# pyIMU_v1.net
KiCad netlist of a schematic drawn in EAGLE
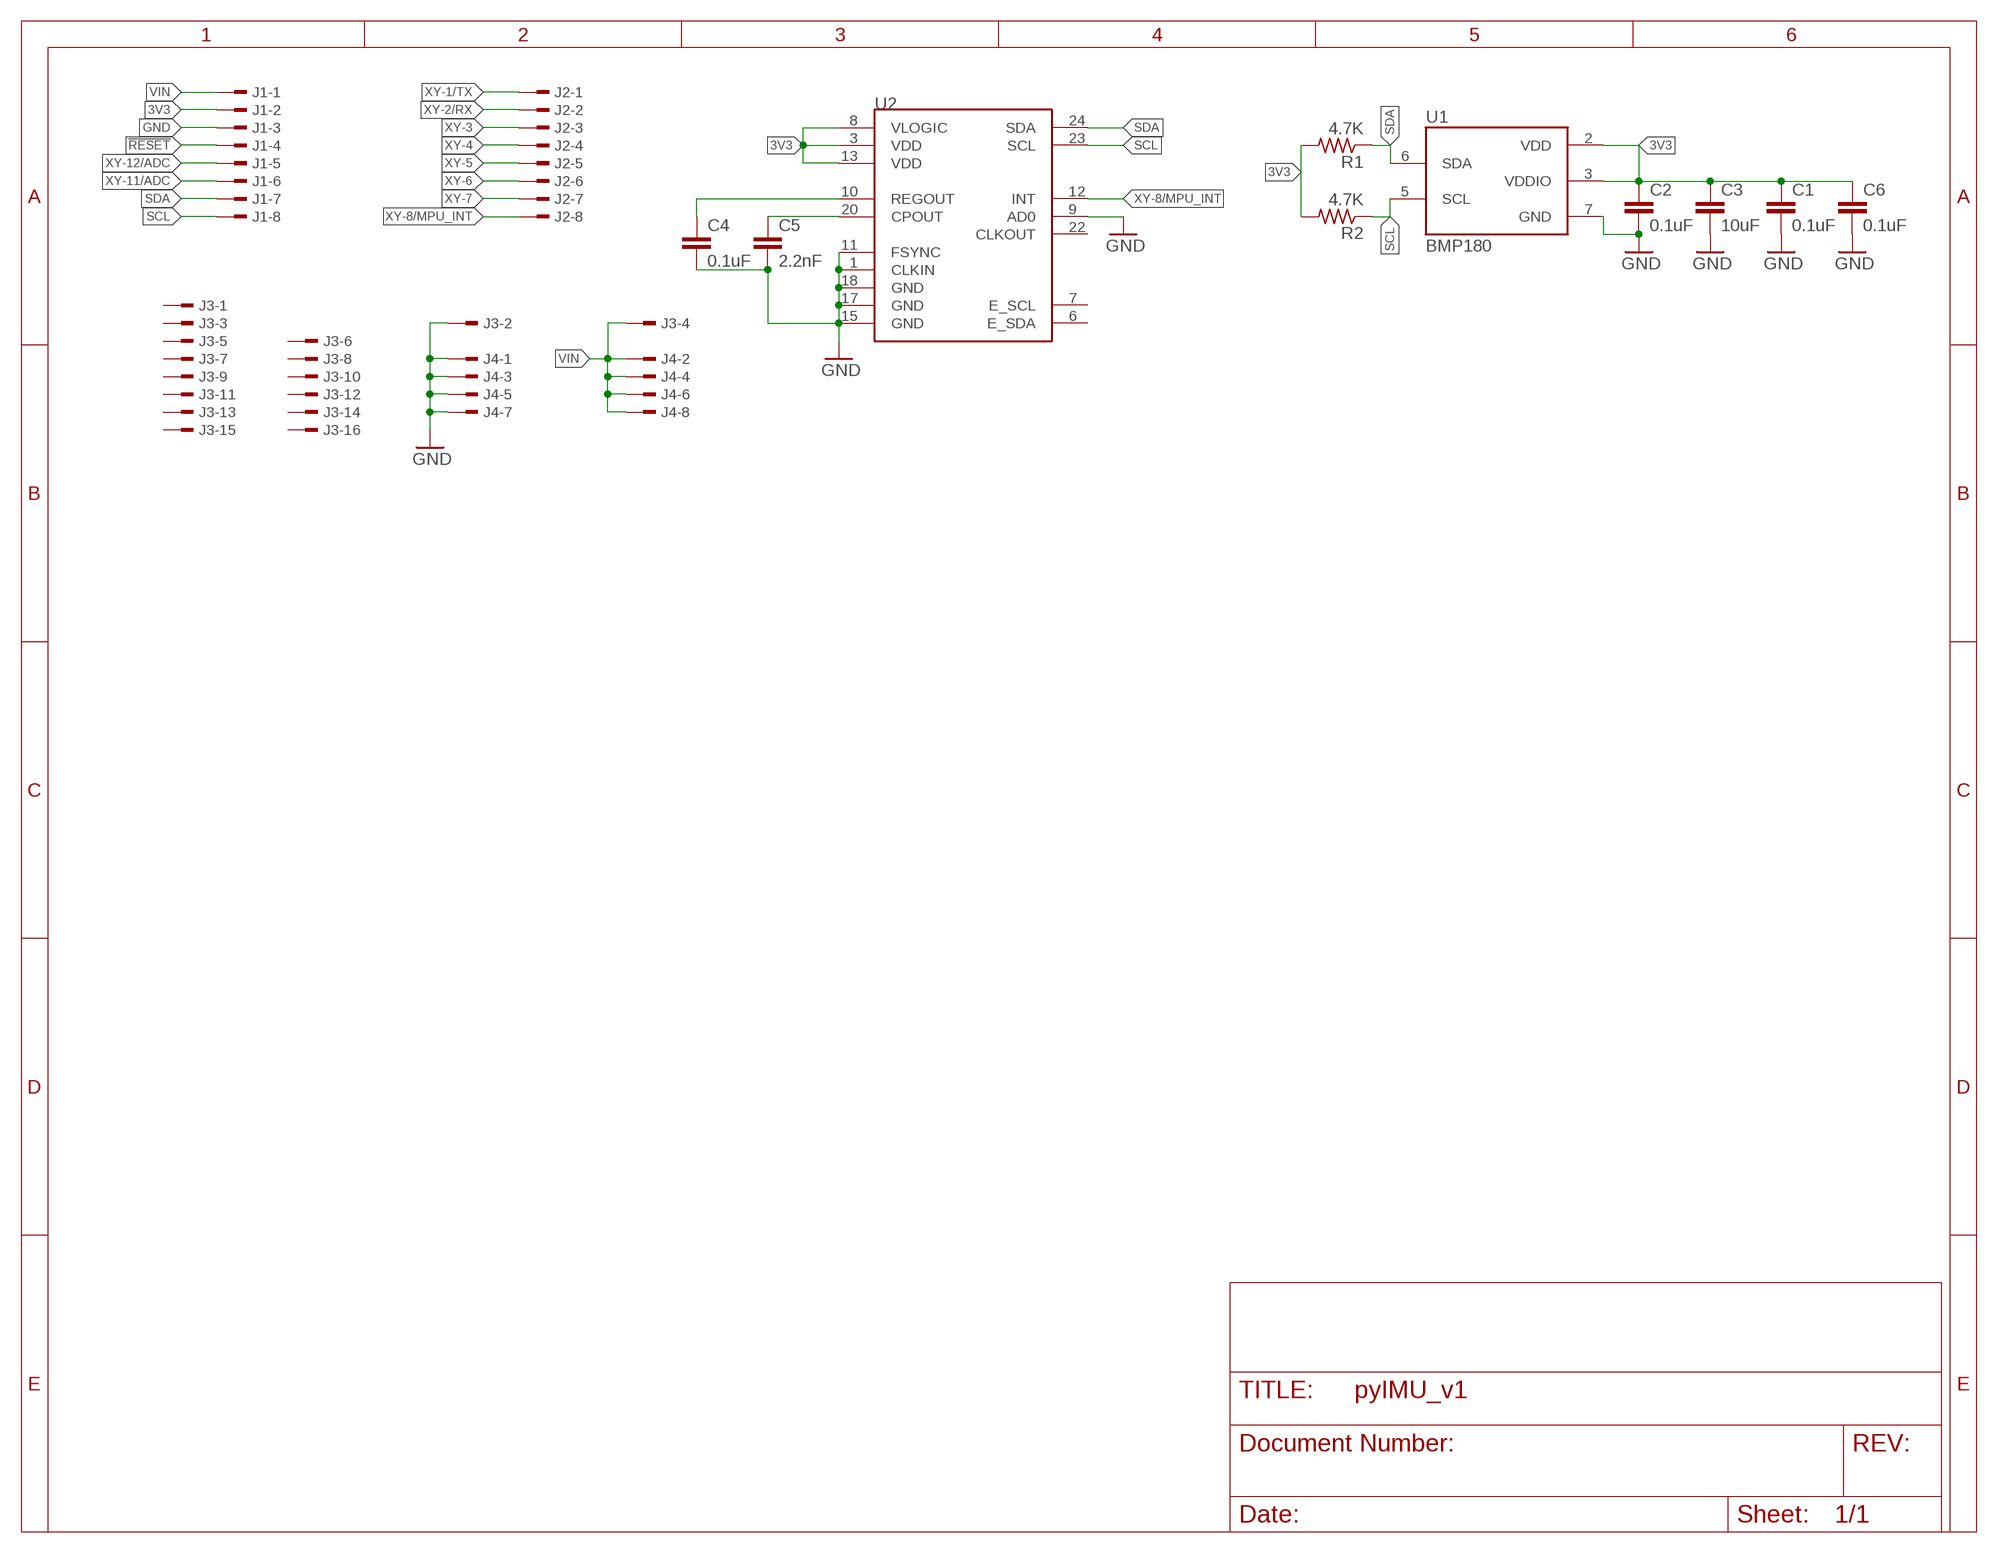
[diagram p0: schematic, sheet 1]

(export (version "E")
  (design (tool "Eeschema 10.0.6"))
  (components
    (comp (ref "C1")
      (value "0.1uF")
      (footprint "eagle-import:C0603K")
      (libsource (lib "eagle-import") (part "C-EUC0603K"))
    )
    (comp (ref "C2")
      (value "0.1uF")
      (footprint "eagle-import:C0603K")
      (libsource (lib "eagle-import") (part "C-EUC0603K"))
    )
    (comp (ref "C3")
      (value "10uF")
      (footprint "eagle-import:C0603K")
      (libsource (lib "eagle-import") (part "C-EUC0603K"))
    )
    (comp (ref "C4")
      (value "0.1uF")
      (footprint "eagle-import:C0603K")
      (libsource (lib "eagle-import") (part "C-EUC0603K"))
    )
    (comp (ref "C5")
      (value "2.2nF")
      (footprint "eagle-import:C0603K")
      (libsource (lib "eagle-import") (part "C-EUC0603K"))
    )
    (comp (ref "C6")
      (value "0.1uF")
      (footprint "eagle-import:C0603K")
      (libsource (lib "eagle-import") (part "C-EUC0603K"))
    )
    (comp (ref "J1")
      (value "TSW-108-02-S-S-MOD")
      (footprint "eagle-import:TSW-108-02-S-S-MOD")
      (libsource (lib "eagle-import") (part "TSW-108-02-S-S-MOD"))
    )
    (comp (ref "J2")
      (value "TSW-108-02-S-S-MOD")
      (footprint "eagle-import:TSW-108-02-S-S-MOD")
      (libsource (lib "eagle-import") (part "TSW-108-02-S-S-MOD"))
    )
    (comp (ref "J3")
      (value "TSW-108-02-S-D-MOD")
      (footprint "eagle-import:TSW-108-02-S-D-MOD")
      (libsource (lib "eagle-import") (part "TSW-108-02-S-D-MOD"))
    )
    (comp (ref "J4")
      (value "TSW-104-02-S-D-MOD")
      (footprint "eagle-import:TSW-104-02-S-D-MOD")
      (libsource (lib "eagle-import") (part "TSW-104-02-S-D-MOD"))
    )
    (comp (ref "R1")
      (value "4.7K")
      (footprint "eagle-import:R0603")
      (libsource (lib "eagle-import") (part "R-US_R0603"))
    )
    (comp (ref "R2")
      (value "4.7K")
      (footprint "eagle-import:R0603")
      (libsource (lib "eagle-import") (part "R-US_R0603"))
    )
    (comp (ref "U1")
      (value "BMP180")
      (footprint "eagle-import:BMP180")
      (libsource (lib "eagle-import") (part "BMP180"))
    )
    (comp (ref "U2")
      (value "MPU-9150QFN-24-NP")
      (footprint "eagle-import:QFN-24-NP")
      (libsource (lib "eagle-import") (part "MPU-9150QFN-24-NP"))
    )
  )
  (nets
    (net (code "1") (name "/~{RESET}") (class "Default")
      (node (ref "J1") (pin "4") (pinfunction "1_4") (pintype "passive"))
    )
    (net (code "2") (name "3V3") (class "Default")
      (node (ref "C1") (pin "1") (pinfunction "1_1") (pintype "passive"))
      (node (ref "C2") (pin "1") (pinfunction "1_1") (pintype "passive"))
      (node (ref "C3") (pin "1") (pinfunction "1_1") (pintype "passive"))
      (node (ref "C6") (pin "1") (pinfunction "1_1") (pintype "passive"))
      (node (ref "J1") (pin "2") (pinfunction "1_2") (pintype "passive"))
      (node (ref "R1") (pin "2") (pinfunction "2_2") (pintype "passive"))
      (node (ref "R2") (pin "2") (pinfunction "2_2") (pintype "passive"))
      (node (ref "U1") (pin "2") (pinfunction "VDD_2") (pintype "power_in"))
      (node (ref "U1") (pin "3") (pinfunction "VDDIO_3") (pintype "power_in"))
      (node (ref "U2") (pin "13") (pinfunction "VDD_13") (pintype "bidirectional"))
      (node (ref "U2") (pin "3") (pinfunction "VDD_3") (pintype "bidirectional"))
      (node (ref "U2") (pin "8") (pinfunction "VLOGIC_8") (pintype "bidirectional"))
    )
    (net (code "3") (name "GND") (class "Default")
      (node (ref "C1") (pin "2") (pinfunction "2_2") (pintype "passive"))
      (node (ref "C2") (pin "2") (pinfunction "2_2") (pintype "passive"))
      (node (ref "C3") (pin "2") (pinfunction "2_2") (pintype "passive"))
      (node (ref "C4") (pin "2") (pinfunction "2_2") (pintype "passive"))
      (node (ref "C5") (pin "2") (pinfunction "2_2") (pintype "passive"))
      (node (ref "C6") (pin "2") (pinfunction "2_2") (pintype "passive"))
      (node (ref "J1") (pin "3") (pinfunction "1_3") (pintype "passive"))
      (node (ref "J3") (pin "2") (pinfunction "1_2") (pintype "passive"))
      (node (ref "J4") (pin "1") (pinfunction "1_1") (pintype "passive"))
      (node (ref "J4") (pin "3") (pinfunction "1_3") (pintype "passive"))
      (node (ref "J4") (pin "5") (pinfunction "1_5") (pintype "passive"))
      (node (ref "J4") (pin "7") (pinfunction "1_7") (pintype "passive"))
      (node (ref "U1") (pin "7") (pinfunction "GND_7") (pintype "power_in"))
      (node (ref "U2") (pin "1") (pinfunction "CLKIN_1") (pintype "bidirectional"))
      (node (ref "U2") (pin "11") (pinfunction "FSYNC_11") (pintype "bidirectional"))
      (node (ref "U2") (pin "15") (pinfunction "GND_15") (pintype "bidirectional"))
      (node (ref "U2") (pin "17") (pinfunction "GND_17") (pintype "bidirectional"))
      (node (ref "U2") (pin "18") (pinfunction "GND_18") (pintype "bidirectional"))
      (node (ref "U2") (pin "9") (pinfunction "AD0_9") (pintype "bidirectional"))
    )
    (net (code "4") (name "Net-(U2-CPOUT)") (class "Default")
      (node (ref "C5") (pin "1") (pinfunction "1_1") (pintype "passive"))
      (node (ref "U2") (pin "20") (pinfunction "CPOUT_20") (pintype "bidirectional"))
    )
    (net (code "5") (name "Net-(U2-REGOUT)") (class "Default")
      (node (ref "C4") (pin "1") (pinfunction "1_1") (pintype "passive"))
      (node (ref "U2") (pin "10") (pinfunction "REGOUT_10") (pintype "bidirectional"))
    )
    (net (code "6") (name "SCL") (class "Default")
      (node (ref "J1") (pin "8") (pinfunction "1_8") (pintype "passive"))
      (node (ref "R2") (pin "1") (pinfunction "1_1") (pintype "passive"))
      (node (ref "U1") (pin "5") (pinfunction "SCL_5") (pintype "input"))
      (node (ref "U2") (pin "23") (pinfunction "SCL_23") (pintype "bidirectional"))
    )
    (net (code "7") (name "SDA") (class "Default")
      (node (ref "J1") (pin "7") (pinfunction "1_7") (pintype "passive"))
      (node (ref "R1") (pin "1") (pinfunction "1_1") (pintype "passive"))
      (node (ref "U1") (pin "6") (pinfunction "SDA_6") (pintype "bidirectional"))
      (node (ref "U2") (pin "24") (pinfunction "SDA_24") (pintype "bidirectional"))
    )
    (net (code "8") (name "VIN") (class "Default")
      (node (ref "J1") (pin "1") (pinfunction "1_1") (pintype "passive"))
      (node (ref "J3") (pin "4") (pinfunction "1_4") (pintype "passive"))
      (node (ref "J4") (pin "2") (pinfunction "1_2") (pintype "passive"))
      (node (ref "J4") (pin "4") (pinfunction "1_4") (pintype "passive"))
      (node (ref "J4") (pin "6") (pinfunction "1_6") (pintype "passive"))
      (node (ref "J4") (pin "8") (pinfunction "1_8") (pintype "passive"))
    )
    (net (code "9") (name "XY-1{slash}TX") (class "Default")
      (node (ref "J2") (pin "1") (pinfunction "1_1") (pintype "passive"))
    )
    (net (code "10") (name "XY-2{slash}RX") (class "Default")
      (node (ref "J2") (pin "2") (pinfunction "1_2") (pintype "passive"))
    )
    (net (code "11") (name "XY-3") (class "Default")
      (node (ref "J2") (pin "3") (pinfunction "1_3") (pintype "passive"))
    )
    (net (code "12") (name "XY-4") (class "Default")
      (node (ref "J2") (pin "4") (pinfunction "1_4") (pintype "passive"))
    )
    (net (code "13") (name "XY-5") (class "Default")
      (node (ref "J2") (pin "5") (pinfunction "1_5") (pintype "passive"))
    )
    (net (code "14") (name "XY-6") (class "Default")
      (node (ref "J2") (pin "6") (pinfunction "1_6") (pintype "passive"))
    )
    (net (code "15") (name "XY-7") (class "Default")
      (node (ref "J2") (pin "7") (pinfunction "1_7") (pintype "passive"))
    )
    (net (code "16") (name "XY-8{slash}MPU_INT") (class "Default")
      (node (ref "J2") (pin "8") (pinfunction "1_8") (pintype "passive"))
      (node (ref "U2") (pin "12") (pinfunction "INT_12") (pintype "bidirectional"))
    )
    (net (code "17") (name "XY-11{slash}ADC") (class "Default")
      (node (ref "J1") (pin "6") (pinfunction "1_6") (pintype "passive"))
    )
    (net (code "18") (name "XY-12{slash}ADC") (class "Default")
      (node (ref "J1") (pin "5") (pinfunction "1_5") (pintype "passive"))
    )
    (net (code "19") (name "unconnected-(J3-Pad1)") (class "Default")
      (node (ref "J3") (pin "1") (pinfunction "1_1") (pintype "passive"))
    )
    (net (code "20") (name "unconnected-(J3B-1-Pad10)") (class "Default")
      (node (ref "J3") (pin "10") (pinfunction "1_10") (pintype "passive"))
    )
    (net (code "21") (name "unconnected-(J3C-1-Pad11)") (class "Default")
      (node (ref "J3") (pin "11") (pinfunction "1_11") (pintype "passive"))
    )
    (net (code "22") (name "unconnected-(J3D-1-Pad12)") (class "Default")
      (node (ref "J3") (pin "12") (pinfunction "1_12") (pintype "passive"))
    )
    (net (code "23") (name "unconnected-(J3E-1-Pad13)") (class "Default")
      (node (ref "J3") (pin "13") (pinfunction "1_13") (pintype "passive"))
    )
    (net (code "24") (name "unconnected-(J3F-1-Pad14)") (class "Default")
      (node (ref "J3") (pin "14") (pinfunction "1_14") (pintype "passive"))
    )
    (net (code "25") (name "unconnected-(J3G-1-Pad15)") (class "Default")
      (node (ref "J3") (pin "15") (pinfunction "1_15") (pintype "passive"))
    )
    (net (code "26") (name "unconnected-(J3H-1-Pad16)") (class "Default")
      (node (ref "J3") (pin "16") (pinfunction "1_16") (pintype "passive"))
    )
    (net (code "27") (name "unconnected-(J3J-1-Pad3)") (class "Default")
      (node (ref "J3") (pin "3") (pinfunction "1_3") (pintype "passive"))
    )
    (net (code "28") (name "unconnected-(J3L-1-Pad5)") (class "Default")
      (node (ref "J3") (pin "5") (pinfunction "1_5") (pintype "passive"))
    )
    (net (code "29") (name "unconnected-(J3M-1-Pad6)") (class "Default")
      (node (ref "J3") (pin "6") (pinfunction "1_6") (pintype "passive"))
    )
    (net (code "30") (name "unconnected-(J3N-1-Pad7)") (class "Default")
      (node (ref "J3") (pin "7") (pinfunction "1_7") (pintype "passive"))
    )
    (net (code "31") (name "unconnected-(J3O-1-Pad8)") (class "Default")
      (node (ref "J3") (pin "8") (pinfunction "1_8") (pintype "passive"))
    )
    (net (code "32") (name "unconnected-(J3P-1-Pad9)") (class "Default")
      (node (ref "J3") (pin "9") (pinfunction "1_9") (pintype "passive"))
    )
    (net (code "33") (name "unconnected-(U2-CLKOUT-Pad22)") (class "Default")
      (node (ref "U2") (pin "22") (pinfunction "CLKOUT_22") (pintype "bidirectional"))
    )
    (net (code "34") (name "unconnected-(U2-E_SCL-Pad7)") (class "Default")
      (node (ref "U2") (pin "7") (pinfunction "E_SCL_7") (pintype "bidirectional"))
    )
    (net (code "35") (name "unconnected-(U2-E_SDA-Pad6)") (class "Default")
      (node (ref "U2") (pin "6") (pinfunction "E_SDA_6") (pintype "bidirectional"))
    )
  )
)
